# aiotdaan.net
KiCad netlist of a schematic drawn in EAGLE
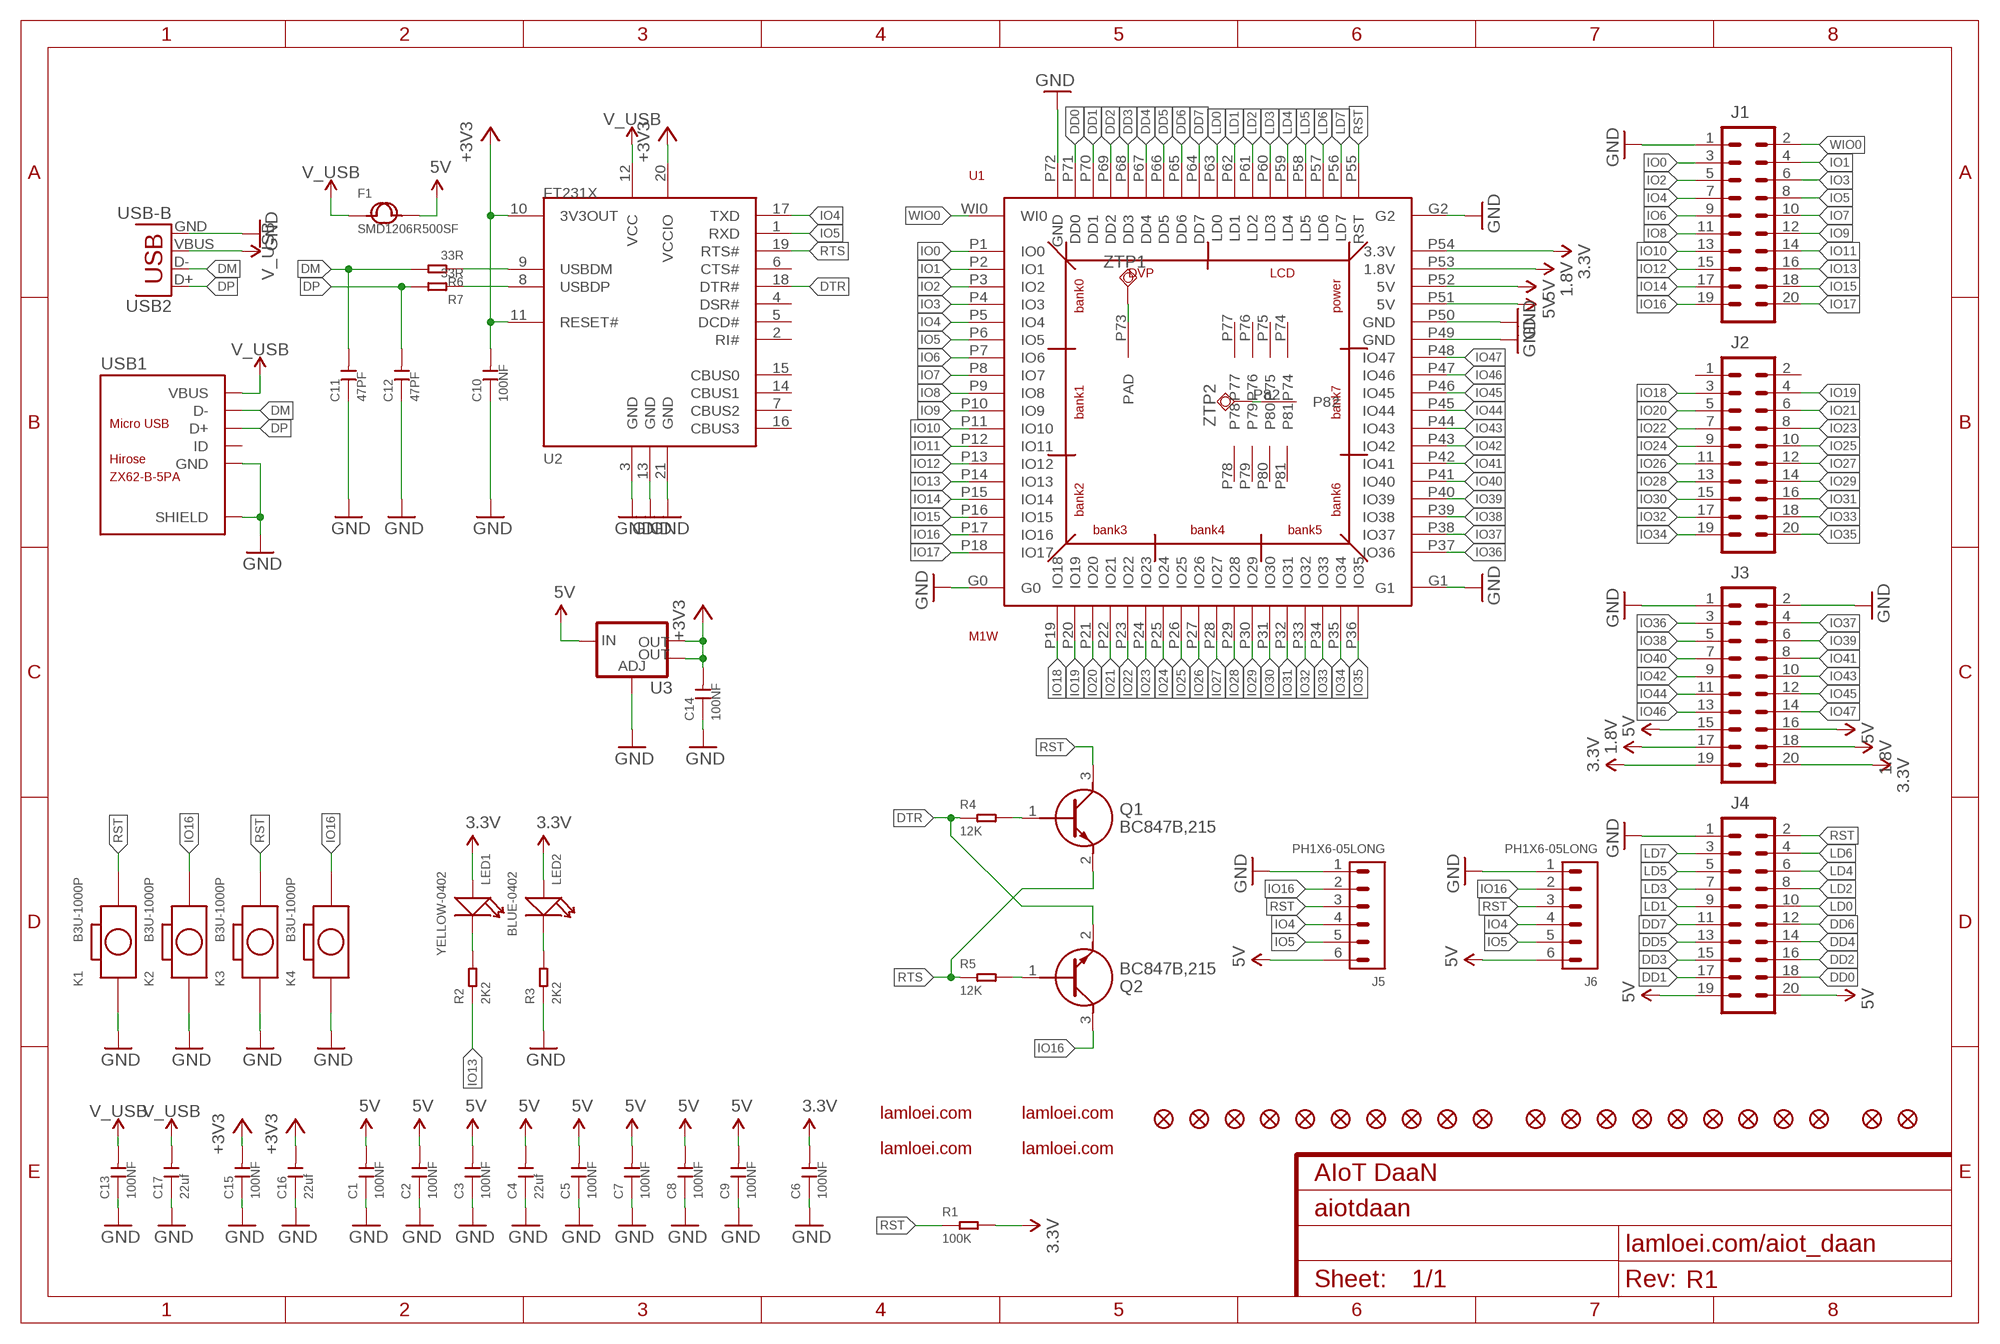
[diagram p0: schematic, sheet 1]

(export (version "E")
  (design (tool "Eeschema 10.0.6"))
  (components
    (comp (ref "C1")
      (value "100NF")
      (footprint "eagle-import:C0402")
      (fields (field (name "MPN") "CC0402JRNPO9BN470"))
      (libsource (lib "eagle-import") (part "CERAMIC-47PF-50V-5%-NP0(0402)"))
    )
    (comp (ref "C2")
      (value "100NF")
      (footprint "eagle-import:C0402")
      (fields (field (name "MPN") "CC0402JRNPO9BN470"))
      (libsource (lib "eagle-import") (part "CERAMIC-47PF-50V-5%-NP0(0402)"))
    )
    (comp (ref "C3")
      (value "100NF")
      (footprint "eagle-import:C0402")
      (fields (field (name "MPN") "CC0402JRNPO9BN470"))
      (libsource (lib "eagle-import") (part "CERAMIC-47PF-50V-5%-NP0(0402)"))
    )
    (comp (ref "C4")
      (value "22uf")
      (footprint "eagle-import:C0805")
      (fields (field (name "MPN") "CC0805MKX5R5BB226"))
      (libsource (lib "eagle-import") (part "CERAMIC-22UF-6.3V-20%-X5R(0805)"))
    )
    (comp (ref "C5")
      (value "100NF")
      (footprint "eagle-import:C0402")
      (fields (field (name "MPN") "CC0402JRNPO9BN470"))
      (libsource (lib "eagle-import") (part "CERAMIC-47PF-50V-5%-NP0(0402)"))
    )
    (comp (ref "C6")
      (value "100NF")
      (footprint "eagle-import:C0402")
      (fields (field (name "MPN") "CC0402JRNPO9BN470"))
      (libsource (lib "eagle-import") (part "CERAMIC-47PF-50V-5%-NP0(0402)"))
    )
    (comp (ref "C7")
      (value "100NF")
      (footprint "eagle-import:C0402")
      (fields (field (name "MPN") "CC0402JRNPO9BN470"))
      (libsource (lib "eagle-import") (part "CERAMIC-47PF-50V-5%-NP0(0402)"))
    )
    (comp (ref "C8")
      (value "100NF")
      (footprint "eagle-import:C0402")
      (fields (field (name "MPN") "CC0402JRNPO9BN470"))
      (libsource (lib "eagle-import") (part "CERAMIC-47PF-50V-5%-NP0(0402)"))
    )
    (comp (ref "C9")
      (value "100NF")
      (footprint "eagle-import:C0402")
      (fields (field (name "MPN") "CC0402JRNPO9BN470"))
      (libsource (lib "eagle-import") (part "CERAMIC-47PF-50V-5%-NP0(0402)"))
    )
    (comp (ref "C10")
      (value "100NF")
      (footprint "eagle-import:C0402")
      (fields (field (name "MPN") "CC0402JRNPO9BN470"))
      (libsource (lib "eagle-import") (part "CERAMIC-47PF-50V-5%-NP0(0402)"))
    )
    (comp (ref "C11")
      (value "47PF")
      (footprint "eagle-import:C0402")
      (fields (field (name "MPN") "CC0402JRNPO9BN470"))
      (libsource (lib "eagle-import") (part "CERAMIC-47PF-50V-5%-NP0(0402)"))
    )
    (comp (ref "C12")
      (value "47PF")
      (footprint "eagle-import:C0402")
      (fields (field (name "MPN") "CC0402JRNPO9BN470"))
      (libsource (lib "eagle-import") (part "CERAMIC-47PF-50V-5%-NP0(0402)"))
    )
    (comp (ref "C13")
      (value "100NF")
      (footprint "eagle-import:C0402")
      (fields (field (name "MPN") "CC0402JRNPO9BN470"))
      (libsource (lib "eagle-import") (part "CERAMIC-47PF-50V-5%-NP0(0402)"))
    )
    (comp (ref "C14")
      (value "100NF")
      (footprint "eagle-import:C0402")
      (fields (field (name "MPN") "CC0402JRNPO9BN470"))
      (libsource (lib "eagle-import") (part "CERAMIC-47PF-50V-5%-NP0(0402)"))
    )
    (comp (ref "C15")
      (value "100NF")
      (footprint "eagle-import:C0402")
      (fields (field (name "MPN") "CC0402JRNPO9BN470"))
      (libsource (lib "eagle-import") (part "CERAMIC-47PF-50V-5%-NP0(0402)"))
    )
    (comp (ref "C16")
      (value "22uf")
      (footprint "eagle-import:C0805")
      (fields (field (name "MPN") "CC0805MKX5R5BB226"))
      (libsource (lib "eagle-import") (part "CERAMIC-22UF-6.3V-20%-X5R(0805)"))
    )
    (comp (ref "C17")
      (value "22uf")
      (footprint "eagle-import:C0805")
      (fields (field (name "MPN") "CC0805MKX5R5BB226"))
      (libsource (lib "eagle-import") (part "CERAMIC-22UF-6.3V-20%-X5R(0805)"))
    )
    (comp (ref "F1")
      (value "SMD1206R500SF")
      (footprint "eagle-import:F1206")
      (libsource (lib "eagle-import") (part "SMD-PPTC-500MA(1206)"))
    )
    (comp (ref "J1")
      (value "M10X2")
      (footprint "eagle-import:2X10")
      (libsource (lib "eagle-import") (part "M10X2"))
    )
    (comp (ref "J2")
      (value "M10X2")
      (footprint "eagle-import:2X10")
      (libsource (lib "eagle-import") (part "M10X2"))
    )
    (comp (ref "J3")
      (value "M10X2")
      (footprint "eagle-import:2X10")
      (libsource (lib "eagle-import") (part "M10X2"))
    )
    (comp (ref "J4")
      (value "M10X2")
      (footprint "eagle-import:2X10")
      (libsource (lib "eagle-import") (part "M10X2"))
    )
    (comp (ref "J5")
      (value "PH1X6-05LONG")
      (footprint "eagle-import:PHL005-1-6")
      (libsource (lib "eagle-import") (part "PH1X6-05LONG"))
    )
    (comp (ref "J6")
      (value "PH1X6-05LONG")
      (footprint "eagle-import:PHL005-1-6")
      (libsource (lib "eagle-import") (part "PH1X6-05LONG"))
    )
    (comp (ref "K1")
      (value "B3U-1000P")
      (footprint "eagle-import:SW2-SMD-3.0X2.5X1.2+0.4MM")
      (libsource (lib "eagle-import") (part "SMD-BUTTON-WITHOUT-BOSS-(2P-3X2.5MM)"))
    )
    (comp (ref "K2")
      (value "B3U-1000P")
      (footprint "eagle-import:SW2-SMD-3.0X2.5X1.2+0.4MM")
      (libsource (lib "eagle-import") (part "SMD-BUTTON-WITHOUT-BOSS-(2P-3X2.5MM)"))
    )
    (comp (ref "K3")
      (value "B3U-1000P")
      (footprint "eagle-import:SW2-SMD-3.0X2.5X1.2+0.4MM")
      (libsource (lib "eagle-import") (part "SMD-BUTTON-WITHOUT-BOSS-(2P-3X2.5MM)"))
    )
    (comp (ref "K4")
      (value "B3U-1000P")
      (footprint "eagle-import:SW2-SMD-3.0X2.5X1.2+0.4MM")
      (libsource (lib "eagle-import") (part "SMD-BUTTON-WITHOUT-BOSS-(2P-3X2.5MM)"))
    )
    (comp (ref "LED1")
      (value "YELLOW-0402")
      (footprint "eagle-import:LED-0402")
      (fields (field (name "MPN") "BL-HB337A-AV-TRB"))
      (libsource (lib "eagle-import") (part "SMD-LED-CLEAR-BLUE(0402)"))
    )
    (comp (ref "LED2")
      (value "BLUE-0402")
      (footprint "eagle-import:LED-0402")
      (fields (field (name "MPN") "BL-HB337A-AV-TRB"))
      (libsource (lib "eagle-import") (part "SMD-LED-CLEAR-BLUE(0402)"))
    )
    (comp (ref "Q1")
      (value "BC847B,215")
      (footprint "eagle-import:SOT95P230X110-3N")
      (fields (field (name "RS_PART_NUMBER") "4367947P"))
      (libsource (lib "eagle-import") (part "BC847B,215"))
    )
    (comp (ref "Q2")
      (value "BC847B,215")
      (footprint "eagle-import:SOT95P230X110-3N")
      (fields (field (name "RS_PART_NUMBER") "4367947P"))
      (libsource (lib "eagle-import") (part "BC847B,215"))
    )
    (comp (ref "R1")
      (value "100K")
      (footprint "eagle-import:R0402")
      (fields (field (name "MPN") "RC0402FR-0722RL"))
      (libsource (lib "eagle-import") (part "SMD-RES-22R-1%-1/16W(0402)"))
    )
    (comp (ref "R2")
      (value "2K2")
      (footprint "eagle-import:R0402")
      (fields (field (name "MPN") "RC0402FR-0722RL"))
      (libsource (lib "eagle-import") (part "SMD-RES-22R-1%-1/16W(0402)"))
    )
    (comp (ref "R3")
      (value "2K2")
      (footprint "eagle-import:R0402")
      (fields (field (name "MPN") "RC0402FR-0722RL"))
      (libsource (lib "eagle-import") (part "SMD-RES-22R-1%-1/16W(0402)"))
    )
    (comp (ref "R4")
      (value "12K")
      (footprint "eagle-import:R0402")
      (fields (field (name "MPN") "RC0402FR-0722RL"))
      (libsource (lib "eagle-import") (part "SMD-RES-22R-1%-1/16W(0402)"))
    )
    (comp (ref "R5")
      (value "12K")
      (footprint "eagle-import:R0402")
      (fields (field (name "MPN") "RC0402FR-0722RL"))
      (libsource (lib "eagle-import") (part "SMD-RES-22R-1%-1/16W(0402)"))
    )
    (comp (ref "R6")
      (value "33R")
      (footprint "eagle-import:R0402")
      (fields (field (name "MPN") "RC0402FR-0722RL"))
      (libsource (lib "eagle-import") (part "SMD-RES-22R-1%-1/16W(0402)"))
    )
    (comp (ref "R7")
      (value "33R")
      (footprint "eagle-import:R0402")
      (fields (field (name "MPN") "RC0402FR-0722RL"))
      (libsource (lib "eagle-import") (part "SMD-RES-22R-1%-1/16W(0402)"))
    )
    (comp (ref "U1")
      (value "M1W")
      (footprint "eagle-import:M1W")
      (libsource (lib "eagle-import") (part "M1W"))
    )
    (comp (ref "U2")
      (value "FT231X-Q")
      (footprint "eagle-import:QFN20")
      (libsource (lib "eagle-import") (part "FT231X-Q"))
    )
    (comp (ref "U3")
      (value "V_REG_LM1117SOT223")
      (footprint "eagle-import:SOT223")
      (libsource (lib "eagle-import") (part "V_REG_LM1117SOT223"))
    )
    (comp (ref "USB1")
      (value "ZX62-B-5PA")
      (footprint "eagle-import:MICRO-USB5+6P-SMD-0.65-AB")
      (libsource (lib "eagle-import") (part "MICRO-USB-SMD(ZX62-B-5PA)"))
    )
    (comp (ref "USB2")
      (value "USB-B")
      (footprint "eagle-import:USB-B-PTH")
      (libsource (lib "eagle-import") (part "USBPTH"))
    )
    (comp (ref "ZFD1")
      (value "FIDUCIAL1X2")
      (footprint "eagle-import:FIDUCIAL-1X2")
      (libsource (lib "eagle-import") (part "FIDUCIAL1X2"))
    )
    (comp (ref "ZFD2")
      (value "FIDUCIAL1X2")
      (footprint "eagle-import:FIDUCIAL-1X2")
      (libsource (lib "eagle-import") (part "FIDUCIAL1X2"))
    )
    (comp (ref "ZFD3")
      (value "FIDUCIAL1X2")
      (footprint "eagle-import:FIDUCIAL-1X2")
      (libsource (lib "eagle-import") (part "FIDUCIAL1X2"))
    )
    (comp (ref "ZFD4")
      (value "FIDUCIAL1X2")
      (footprint "eagle-import:FIDUCIAL-1X2")
      (libsource (lib "eagle-import") (part "FIDUCIAL1X2"))
    )
    (comp (ref "ZFD5")
      (value "FIDUCIAL1X2")
      (footprint "eagle-import:FIDUCIAL-1X2")
      (libsource (lib "eagle-import") (part "FIDUCIAL1X2"))
    )
    (comp (ref "ZFD6")
      (value "FIDUCIAL1X2")
      (footprint "eagle-import:FIDUCIAL-1X2")
      (libsource (lib "eagle-import") (part "FIDUCIAL1X2"))
    )
    (comp (ref "ZFD7")
      (value "FIDUCIAL1X2")
      (footprint "eagle-import:FIDUCIAL-1X2")
      (libsource (lib "eagle-import") (part "FIDUCIAL1X2"))
    )
    (comp (ref "ZFD8")
      (value "FIDUCIAL1X2")
      (footprint "eagle-import:FIDUCIAL-1X2")
      (libsource (lib "eagle-import") (part "FIDUCIAL1X2"))
    )
    (comp (ref "ZFD9")
      (value "FIDUCIAL1X2")
      (footprint "eagle-import:FIDUCIAL-1X2")
      (libsource (lib "eagle-import") (part "FIDUCIAL1X2"))
    )
    (comp (ref "ZFD10")
      (value "FIDUCIAL1X2")
      (footprint "eagle-import:FIDUCIAL-1X2")
      (libsource (lib "eagle-import") (part "FIDUCIAL1X2"))
    )
    (comp (ref "ZFD11")
      (value "FIDUCIAL1X2")
      (footprint "eagle-import:FIDUCIAL-1X2")
      (libsource (lib "eagle-import") (part "FIDUCIAL1X2"))
    )
    (comp (ref "ZFD12")
      (value "FIDUCIAL1X2")
      (footprint "eagle-import:FIDUCIAL-1X2")
      (libsource (lib "eagle-import") (part "FIDUCIAL1X2"))
    )
    (comp (ref "ZFD13")
      (value "FIDUCIAL1X2")
      (footprint "eagle-import:FIDUCIAL-1X2")
      (libsource (lib "eagle-import") (part "FIDUCIAL1X2"))
    )
    (comp (ref "ZFD14")
      (value "FIDUCIAL1X2")
      (footprint "eagle-import:FIDUCIAL-1X2")
      (libsource (lib "eagle-import") (part "FIDUCIAL1X2"))
    )
    (comp (ref "ZFD15")
      (value "FIDUCIAL1X2")
      (footprint "eagle-import:FIDUCIAL-1X2")
      (libsource (lib "eagle-import") (part "FIDUCIAL1X2"))
    )
    (comp (ref "ZFD16")
      (value "FIDUCIAL1X2")
      (footprint "eagle-import:FIDUCIAL-1X2")
      (libsource (lib "eagle-import") (part "FIDUCIAL1X2"))
    )
    (comp (ref "ZFD17")
      (value "FIDUCIAL1X2")
      (footprint "eagle-import:FIDUCIAL-1X2")
      (libsource (lib "eagle-import") (part "FIDUCIAL1X2"))
    )
    (comp (ref "ZFD18")
      (value "FIDUCIAL1X2")
      (footprint "eagle-import:FIDUCIAL-1X2")
      (libsource (lib "eagle-import") (part "FIDUCIAL1X2"))
    )
    (comp (ref "ZFD19")
      (value "FIDUCIAL1X2")
      (footprint "eagle-import:FIDUCIAL-1X2")
      (libsource (lib "eagle-import") (part "FIDUCIAL1X2"))
    )
    (comp (ref "ZFD20")
      (value "FIDUCIAL1X2")
      (footprint "eagle-import:FIDUCIAL-1X2")
      (libsource (lib "eagle-import") (part "FIDUCIAL1X2"))
    )
    (comp (ref "ZFD21")
      (value "FIDUCIAL1X2")
      (footprint "eagle-import:FIDUCIAL-1X2")
      (libsource (lib "eagle-import") (part "FIDUCIAL1X2"))
    )
    (comp (ref "ZL1")
      (value "LAMLOEI_BIGLOGO")
      (footprint "eagle-import:LAMLOEI_BIGLOGO")
      (libsource (lib "eagle-import") (part "LAMLOEI_BIGLOGO"))
    )
    (comp (ref "ZL2")
      (value "LAMLOEI_BIGLOGO")
      (footprint "eagle-import:LAMLOEI_BIGLOGO")
      (libsource (lib "eagle-import") (part "LAMLOEI_BIGLOGO"))
    )
    (comp (ref "ZL3")
      (value "LAMLEOI_LOGO_3")
      (footprint "eagle-import:LAMLEOI_LOGO_3")
      (libsource (lib "eagle-import") (part "LAMLEOI_LOGO_3"))
    )
    (comp (ref "ZL4")
      (value "LAMLEOI_LOGO_3")
      (footprint "eagle-import:LAMLEOI_LOGO_3")
      (libsource (lib "eagle-import") (part "LAMLEOI_LOGO_3"))
    )
    (comp (ref "ZTP1")
      (value "TPSQTP20SQ")
      (footprint "eagle-import:TP20SQ")
      (libsource (lib "eagle-import") (part "TPSQTP20SQ"))
    )
    (comp (ref "ZTP2")
      (value "TPSQTP20SQ")
      (footprint "eagle-import:TP20SQ")
      (libsource (lib "eagle-import") (part "TPSQTP20SQ"))
    )
  )
  (nets
    (net (code "1") (name "+3V3") (class "Default")
      (node (ref "C10") (pin "2") (pinfunction "2_2") (pintype "passive"))
      (node (ref "C14") (pin "2") (pinfunction "2_2") (pintype "passive"))
      (node (ref "C15") (pin "2") (pinfunction "2_2") (pintype "passive"))
      (node (ref "C16") (pin "2") (pinfunction "2_2") (pintype "passive"))
      (node (ref "U2") (pin "10") (pinfunction "3V3OUT_10") (pintype "bidirectional"))
      (node (ref "U2") (pin "11") (pinfunction "RESET#_11") (pintype "bidirectional"))
      (node (ref "U2") (pin "20") (pinfunction "VCCIO_20") (pintype "bidirectional"))
      (node (ref "U3") (pin "2") (pinfunction "OUT_2") (pintype "output"))
      (node (ref "U3") (pin "4") (pinfunction "OUT_4") (pintype "output"))
    )
    (net (code "2") (name "1.8V") (class "Default")
      (node (ref "J3") (pin "17") (pinfunction "17_17") (pintype "passive"))
      (node (ref "J3") (pin "18") (pinfunction "18_18") (pintype "passive"))
      (node (ref "U1") (pin "P53") (pinfunction "1.8V_P53") (pintype "power_in"))
    )
    (net (code "3") (name "3.3V") (class "Default")
      (node (ref "C6") (pin "2") (pinfunction "2_2") (pintype "passive"))
      (node (ref "J3") (pin "19") (pinfunction "19_19") (pintype "passive"))
      (node (ref "J3") (pin "20") (pinfunction "20_20") (pintype "passive"))
      (node (ref "LED1") (pin "+") (pinfunction "+_+") (pintype "passive"))
      (node (ref "LED2") (pin "+") (pinfunction "+_+") (pintype "passive"))
      (node (ref "R1") (pin "2") (pinfunction "2_2") (pintype "passive"))
      (node (ref "U1") (pin "P54") (pinfunction "3.3V_P54") (pintype "power_in"))
    )
    (net (code "4") (name "5V") (class "Default")
      (node (ref "C1") (pin "2") (pinfunction "2_2") (pintype "passive"))
      (node (ref "C2") (pin "2") (pinfunction "2_2") (pintype "passive"))
      (node (ref "C3") (pin "2") (pinfunction "2_2") (pintype "passive"))
      (node (ref "C4") (pin "2") (pinfunction "2_2") (pintype "passive"))
      (node (ref "C5") (pin "2") (pinfunction "2_2") (pintype "passive"))
      (node (ref "C7") (pin "2") (pinfunction "2_2") (pintype "passive"))
      (node (ref "C8") (pin "2") (pinfunction "2_2") (pintype "passive"))
      (node (ref "C9") (pin "2") (pinfunction "2_2") (pintype "passive"))
      (node (ref "F1") (pin "2") (pinfunction "2_2") (pintype "bidirectional"))
      (node (ref "J3") (pin "15") (pinfunction "15_15") (pintype "passive"))
      (node (ref "J3") (pin "16") (pinfunction "16_16") (pintype "passive"))
      (node (ref "J4") (pin "19") (pinfunction "19_19") (pintype "passive"))
      (node (ref "J4") (pin "20") (pinfunction "20_20") (pintype "passive"))
      (node (ref "J5") (pin "6") (pinfunction "6_6") (pintype "bidirectional"))
      (node (ref "J6") (pin "6") (pinfunction "6_6") (pintype "bidirectional"))
      (node (ref "U1") (pin "P51") (pinfunction "5V_P51") (pintype "power_in"))
      (node (ref "U1") (pin "P52") (pinfunction "5V_P52") (pintype "power_in"))
      (node (ref "U3") (pin "3") (pinfunction "IN_3") (pintype "input"))
    )
    (net (code "5") (name "DD0") (class "Default")
      (node (ref "J4") (pin "18") (pinfunction "18_18") (pintype "passive"))
      (node (ref "U1") (pin "P71") (pinfunction "DD0_P71") (pintype "bidirectional"))
    )
    (net (code "6") (name "DD1") (class "Default")
      (node (ref "J4") (pin "17") (pinfunction "17_17") (pintype "passive"))
      (node (ref "U1") (pin "P70") (pinfunction "DD1_P70") (pintype "bidirectional"))
    )
    (net (code "7") (name "DD2") (class "Default")
      (node (ref "J4") (pin "16") (pinfunction "16_16") (pintype "passive"))
      (node (ref "U1") (pin "P69") (pinfunction "DD2_P69") (pintype "bidirectional"))
    )
    (net (code "8") (name "DD3") (class "Default")
      (node (ref "J4") (pin "15") (pinfunction "15_15") (pintype "passive"))
      (node (ref "U1") (pin "P68") (pinfunction "DD3_P68") (pintype "bidirectional"))
    )
    (net (code "9") (name "DD4") (class "Default")
      (node (ref "J4") (pin "14") (pinfunction "14_14") (pintype "passive"))
      (node (ref "U1") (pin "P67") (pinfunction "DD4_P67") (pintype "bidirectional"))
    )
    (net (code "10") (name "DD5") (class "Default")
      (node (ref "J4") (pin "13") (pinfunction "13_13") (pintype "passive"))
      (node (ref "U1") (pin "P66") (pinfunction "DD5_P66") (pintype "bidirectional"))
    )
    (net (code "11") (name "DD6") (class "Default")
      (node (ref "J4") (pin "12") (pinfunction "12_12") (pintype "passive"))
      (node (ref "U1") (pin "P65") (pinfunction "DD6_P65") (pintype "bidirectional"))
    )
    (net (code "12") (name "DD7") (class "Default")
      (node (ref "J4") (pin "11") (pinfunction "11_11") (pintype "passive"))
      (node (ref "U1") (pin "P64") (pinfunction "DD7_P64") (pintype "bidirectional"))
    )
    (net (code "13") (name "DM") (class "Default")
      (node (ref "C11") (pin "2") (pinfunction "2_2") (pintype "passive"))
      (node (ref "R6") (pin "2") (pinfunction "2_2") (pintype "passive"))
      (node (ref "USB1") (pin "2") (pinfunction "D-_2") (pintype "bidirectional"))
      (node (ref "USB2") (pin "D-") (pinfunction "D-_D-") (pintype "bidirectional"))
    )
    (net (code "14") (name "DP") (class "Default")
      (node (ref "C12") (pin "2") (pinfunction "2_2") (pintype "passive"))
      (node (ref "R7") (pin "2") (pinfunction "2_2") (pintype "passive"))
      (node (ref "USB1") (pin "3") (pinfunction "D+_3") (pintype "bidirectional"))
      (node (ref "USB2") (pin "D+") (pinfunction "D+_D+") (pintype "bidirectional"))
    )
    (net (code "15") (name "DTR") (class "Default")
      (node (ref "Q2") (pin "2") (pinfunction "E_2") (pintype "bidirectional"))
      (node (ref "R4") (pin "1") (pinfunction "1_1") (pintype "passive"))
      (node (ref "U2") (pin "18") (pinfunction "DTR#_18") (pintype "bidirectional"))
    )
    (net (code "16") (name "GND") (class "Default")
      (node (ref "C1") (pin "1") (pinfunction "1_1") (pintype "passive"))
      (node (ref "C10") (pin "1") (pinfunction "1_1") (pintype "passive"))
      (node (ref "C11") (pin "1") (pinfunction "1_1") (pintype "passive"))
      (node (ref "C12") (pin "1") (pinfunction "1_1") (pintype "passive"))
      (node (ref "C13") (pin "1") (pinfunction "1_1") (pintype "passive"))
      (node (ref "C14") (pin "1") (pinfunction "1_1") (pintype "passive"))
      (node (ref "C15") (pin "1") (pinfunction "1_1") (pintype "passive"))
      (node (ref "C16") (pin "1") (pinfunction "1_1") (pintype "passive"))
      (node (ref "C17") (pin "1") (pinfunction "1_1") (pintype "passive"))
      (node (ref "C2") (pin "1") (pinfunction "1_1") (pintype "passive"))
      (node (ref "C3") (pin "1") (pinfunction "1_1") (pintype "passive"))
      (node (ref "C4") (pin "1") (pinfunction "1_1") (pintype "passive"))
      (node (ref "C5") (pin "1") (pinfunction "1_1") (pintype "passive"))
      (node (ref "C6") (pin "1") (pinfunction "1_1") (pintype "passive"))
      (node (ref "C7") (pin "1") (pinfunction "1_1") (pintype "passive"))
      (node (ref "C8") (pin "1") (pinfunction "1_1") (pintype "passive"))
      (node (ref "C9") (pin "1") (pinfunction "1_1") (pintype "passive"))
      (node (ref "J1") (pin "1") (pinfunction "1_1") (pintype "passive"))
      (node (ref "J3") (pin "1") (pinfunction "1_1") (pintype "passive"))
      (node (ref "J3") (pin "2") (pinfunction "2_2") (pintype "passive"))
      (node (ref "J4") (pin "1") (pinfunction "1_1") (pintype "passive"))
      (node (ref "J5") (pin "1") (pinfunction "1_1") (pintype "bidirectional"))
      (node (ref "J6") (pin "1") (pinfunction "1_1") (pintype "bidirectional"))
      (node (ref "K1") (pin "1") (pinfunction "1_1") (pintype "bidirectional"))
      (node (ref "K2") (pin "1") (pinfunction "1_1") (pintype "bidirectional"))
      (node (ref "K3") (pin "1") (pinfunction "1_1") (pintype "bidirectional"))
      (node (ref "K4") (pin "1") (pinfunction "1_1") (pintype "bidirectional"))
      (node (ref "R3") (pin "1") (pinfunction "1_1") (pintype "passive"))
      (node (ref "U1") (pin "G0") (pinfunction "G0_G0") (pintype "power_in"))
      (node (ref "U1") (pin "G1") (pinfunction "G1_G1") (pintype "power_in"))
      (node (ref "U1") (pin "G2") (pinfunction "G2_G2") (pintype "power_in"))
      (node (ref "U1") (pin "P49") (pinfunction "GND_P49") (pintype "power_in"))
      (node (ref "U1") (pin "P50") (pinfunction "GND_P50") (pintype "power_in"))
      (node (ref "U1") (pin "P72") (pinfunction "GND_P72") (pintype "power_in"))
      (node (ref "U2") (pin "13") (pinfunction "GND_13") (pintype "bidirectional"))
      (node (ref "U2") (pin "21") (pinfunction "GND_21") (pintype "bidirectional"))
      (node (ref "U2") (pin "3") (pinfunction "GND_3") (pintype "bidirectional"))
      (node (ref "U3") (pin "1") (pinfunction "ADJ_1") (pintype "input"))
      (node (ref "USB1") (pin "5") (pinfunction "GND_5") (pintype "power_in"))
      (node (ref "USB1") (pin "P1") (pinfunction "SHIELD_P1") (pintype "power_in"))
      (node (ref "USB1") (pin "P2") (pinfunction "SHIELD_P2") (pintype "power_in"))
      (node (ref "USB1") (pin "P3") (pinfunction "SHIELD_P3") (pintype "power_in"))
      (node (ref "USB1") (pin "P4") (pinfunction "SHIELD_P4") (pintype "power_in"))
      (node (ref "USB1") (pin "P5") (pinfunction "SHIELD_P5") (pintype "power_in"))
      (node (ref "USB1") (pin "P6") (pinfunction "SHIELD_P6") (pintype "power_in"))
      (node (ref "USB2") (pin "GND") (pinfunction "GND_GND") (pintype "bidirectional"))
    )
    (net (code "17") (name "IO0") (class "Default")
      (node (ref "J1") (pin "3") (pinfunction "3_3") (pintype "passive"))
      (node (ref "U1") (pin "P1") (pinfunction "IO0_P1") (pintype "bidirectional"))
    )
    (net (code "18") (name "IO1") (class "Default")
      (node (ref "J1") (pin "4") (pinfunction "4_4") (pintype "passive"))
      (node (ref "U1") (pin "P2") (pinfunction "IO1_P2") (pintype "bidirectional"))
    )
    (net (code "19") (name "IO2") (class "Default")
      (node (ref "J1") (pin "5") (pinfunction "5_5") (pintype "passive"))
      (node (ref "U1") (pin "P3") (pinfunction "IO2_P3") (pintype "bidirectional"))
    )
    (net (code "20") (name "IO3") (class "Default")
      (node (ref "J1") (pin "6") (pinfunction "6_6") (pintype "passive"))
      (node (ref "U1") (pin "P4") (pinfunction "IO3_P4") (pintype "bidirectional"))
    )
    (net (code "21") (name "IO4") (class "Default")
      (node (ref "J1") (pin "7") (pinfunction "7_7") (pintype "passive"))
      (node (ref "J5") (pin "4") (pinfunction "4_4") (pintype "bidirectional"))
      (node (ref "J6") (pin "4") (pinfunction "4_4") (pintype "bidirectional"))
      (node (ref "U1") (pin "P5") (pinfunction "IO4_P5") (pintype "bidirectional"))
      (node (ref "U2") (pin "17") (pinfunction "TXD_17") (pintype "bidirectional"))
    )
    (net (code "22") (name "IO5") (class "Default")
      (node (ref "J1") (pin "8") (pinfunction "8_8") (pintype "passive"))
      (node (ref "J5") (pin "5") (pinfunction "5_5") (pintype "bidirectional"))
      (node (ref "J6") (pin "5") (pinfunction "5_5") (pintype "bidirectional"))
      (node (ref "U1") (pin "P6") (pinfunction "IO5_P6") (pintype "bidirectional"))
      (node (ref "U2") (pin "1") (pinfunction "RXD_1") (pintype "bidirectional"))
    )
    (net (code "23") (name "IO6") (class "Default")
      (node (ref "J1") (pin "9") (pinfunction "9_9") (pintype "passive"))
      (node (ref "U1") (pin "P7") (pinfunction "IO6_P7") (pintype "bidirectional"))
    )
    (net (code "24") (name "IO7") (class "Default")
      (node (ref "J1") (pin "10") (pinfunction "10_10") (pintype "passive"))
      (node (ref "U1") (pin "P8") (pinfunction "IO7_P8") (pintype "bidirectional"))
    )
    (net (code "25") (name "IO8") (class "Default")
      (node (ref "J1") (pin "11") (pinfunction "11_11") (pintype "passive"))
      (node (ref "U1") (pin "P9") (pinfunction "IO8_P9") (pintype "bidirectional"))
    )
    (net (code "26") (name "IO9") (class "Default")
      (node (ref "J1") (pin "12") (pinfunction "12_12") (pintype "passive"))
      (node (ref "U1") (pin "P10") (pinfunction "IO9_P10") (pintype "bidirectional"))
    )
    (net (code "27") (name "IO10") (class "Default")
      (node (ref "J1") (pin "13") (pinfunction "13_13") (pintype "passive"))
      (node (ref "U1") (pin "P11") (pinfunction "IO10_P11") (pintype "bidirectional"))
    )
    (net (code "28") (name "IO11") (class "Default")
      (node (ref "J1") (pin "14") (pinfunction "14_14") (pintype "passive"))
      (node (ref "U1") (pin "P12") (pinfunction "IO11_P12") (pintype "bidirectional"))
    )
    (net (code "29") (name "IO12") (class "Default")
      (node (ref "J1") (pin "15") (pinfunction "15_15") (pintype "passive"))
      (node (ref "U1") (pin "P13") (pinfunction "IO12_P13") (pintype "bidirectional"))
    )
    (net (code "30") (name "IO13") (class "Default")
      (node (ref "J1") (pin "16") (pinfunction "16_16") (pintype "passive"))
      (node (ref "R2") (pin "1") (pinfunction "1_1") (pintype "passive"))
      (node (ref "U1") (pin "P14") (pinfunction "IO13_P14") (pintype "bidirectional"))
    )
    (net (code "31") (name "IO14") (class "Default")
      (node (ref "J1") (pin "17") (pinfunction "17_17") (pintype "passive"))
      (node (ref "U1") (pin "P15") (pinfunction "IO14_P15") (pintype "bidirectional"))
    )
    (net (code "32") (name "IO15") (class "Default")
      (node (ref "J1") (pin "18") (pinfunction "18_18") (pintype "passive"))
      (node (ref "U1") (pin "P16") (pinfunction "IO15_P16") (pintype "bidirectional"))
    )
    (net (code "33") (name "IO16") (class "Default")
      (node (ref "J1") (pin "19") (pinfunction "19_19") (pintype "passive"))
      (node (ref "J5") (pin "2") (pinfunction "2_2") (pintype "bidirectional"))
      (node (ref "J6") (pin "2") (pinfunction "2_2") (pintype "bidirectional"))
      (node (ref "K2") (pin "2") (pinfunction "2_2") (pintype "bidirectional"))
      (node (ref "K4") (pin "2") (pinfunction "2_2") (pintype "bidirectional"))
      (node (ref "Q2") (pin "3") (pinfunction "C_3") (pintype "bidirectional"))
      (node (ref "U1") (pin "P17") (pinfunction "IO16_P17") (pintype "bidirectional"))
    )
    (net (code "34") (name "IO17") (class "Default")
      (node (ref "J1") (pin "20") (pinfunction "20_20") (pintype "passive"))
      (node (ref "U1") (pin "P18") (pinfunction "IO17_P18") (pintype "bidirectional"))
    )
    (net (code "35") (name "IO18") (class "Default")
      (node (ref "J2") (pin "3") (pinfunction "3_3") (pintype "passive"))
      (node (ref "U1") (pin "P19") (pinfunction "IO18_P19") (pintype "bidirectional"))
    )
    (net (code "36") (name "IO19") (class "Default")
      (node (ref "J2") (pin "4") (pinfunction "4_4") (pintype "passive"))
      (node (ref "U1") (pin "P20") (pinfunction "IO19_P20") (pintype "bidirectional"))
    )
    (net (code "37") (name "IO20") (class "Default")
      (node (ref "J2") (pin "5") (pinfunction "5_5") (pintype "passive"))
      (node (ref "U1") (pin "P21") (pinfunction "IO20_P21") (pintype "bidirectional"))
    )
    (net (code "38") (name "IO21") (class "Default")
      (node (ref "J2") (pin "6") (pinfunction "6_6") (pintype "passive"))
      (node (ref "U1") (pin "P22") (pinfunction "IO21_P22") (pintype "bidirectional"))
    )
    (net (code "39") (name "IO22") (class "Default")
      (node (ref "J2") (pin "7") (pinfunction "7_7") (pintype "passive"))
      (node (ref "U1") (pin "P23") (pinfunction "IO22_P23") (pintype "bidirectional"))
    )
    (net (code "40") (name "IO23") (class "Default")
      (node (ref "J2") (pin "8") (pinfunction "8_8") (pintype "passive"))
      (node (ref "U1") (pin "P24") (pinfunction "IO23_P24") (pintype "bidirectional"))
    )
    (net (code "41") (name "IO24") (class "Default")
      (node (ref "J2") (pin "9") (pinfunction "9_9") (pintype "passive"))
      (node (ref "U1") (pin "P25") (pinfunction "IO24_P25") (pintype "bidirectional"))
    )
    (net (code "42") (name "IO25") (class "Default")
      (node (ref "J2") (pin "10") (pinfunction "10_10") (pintype "passive"))
      (node (ref "U1") (pin "P26") (pinfunction "IO25_P26") (pintype "bidirectional"))
    )
    (net (code "43") (name "IO26") (class "Default")
      (node (ref "J2") (pin "11") (pinfunction "11_11") (pintype "passive"))
      (node (ref "U1") (pin "P27") (pinfunction "IO26_P27") (pintype "bidirectional"))
    )
    (net (code "44") (name "IO27") (class "Default")
      (node (ref "J2") (pin "12") (pinfunction "12_12") (pintype "passive"))
      (node (ref "U1") (pin "P28") (pinfunction "IO27_P28") (pintype "bidirectional"))
    )
    (net (code "45") (name "IO28") (class "Default")
      (node (ref "J2") (pin "13") (pinfunction "13_13") (pintype "passive"))
      (node (ref "U1") (pin "P29") (pinfunction "IO28_P29") (pintype "bidirectional"))
    )
    (net (code "46") (name "IO29") (class "Default")
      (node (ref "J2") (pin "14") (pinfunction "14_14") (pintype "passive"))
      (node (ref "U1") (pin "P30") (pinfunction "IO29_P30") (pintype "bidirectional"))
    )
    (net (code "47") (name "IO30") (class "Default")
      (node (ref "J2") (pin "15") (pinfunction "15_15") (pintype "passive"))
      (node (ref "U1") (pin "P31") (pinfunction "IO30_P31") (pintype "bidirectional"))
    )
    (net (code "48") (name "IO31") (class "Default")
      (node (ref "J2") (pin "16") (pinfunction "16_16") (pintype "passive"))
      (node (ref "U1") (pin "P32") (pinfunction "IO31_P32") (pintype "bidirectional"))
    )
    (net (code "49") (name "IO32") (class "Default")
      (node (ref "J2") (pin "17") (pinfunction "17_17") (pintype "passive"))
      (node (ref "U1") (pin "P33") (pinfunction "IO32_P33") (pintype "bidirectional"))
    )
    (net (code "50") (name "IO33") (class "Default")
      (node (ref "J2") (pin "18") (pinfunction "18_18") (pintype "passive"))
      (node (ref "U1") (pin "P34") (pinfunction "IO33_P34") (pintype "bidirectional"))
    )
    (net (code "51") (name "IO34") (class "Default")
      (node (ref "J2") (pin "19") (pinfunction "19_19") (pintype "passive"))
      (node (ref "U1") (pin "P35") (pinfunction "IO34_P35") (pintype "bidirectional"))
    )
    (net (code "52") (name "IO35") (class "Default")
      (node (ref "J2") (pin "20") (pinfunction "20_20") (pintype "passive"))
      (node (ref "U1") (pin "P36") (pinfunction "IO35_P36") (pintype "bidirectional"))
    )
    (net (code "53") (name "IO36") (class "Default")
      (node (ref "J3") (pin "3") (pinfunction "3_3") (pintype "passive"))
      (node (ref "U1") (pin "P37") (pinfunction "IO36_P37") (pintype "bidirectional"))
    )
    (net (code "54") (name "IO37") (class "Default")
      (node (ref "J3") (pin "4") (pinfunction "4_4") (pintype "passive"))
      (node (ref "U1") (pin "P38") (pinfunction "IO37_P38") (pintype "bidirectional"))
    )
    (net (code "55") (name "IO38") (class "Default")
      (node (ref "J3") (pin "5") (pinfunction "5_5") (pintype "passive"))
      (node (ref "U1") (pin "P39") (pinfunction "IO38_P39") (pintype "bidirectional"))
    )
    (net (code "56") (name "IO39") (class "Default")
      (node (ref "J3") (pin "6") (pinfunction "6_6") (pintype "passive"))
      (node (ref "U1") (pin "P40") (pinfunction "IO39_P40") (pintype "bidirectional"))
    )
    (net (code "57") (name "IO40") (class "Default")
      (node (ref "J3") (pin "7") (pinfunction "7_7") (pintype "passive"))
      (node (ref "U1") (pin "P41") (pinfunction "IO40_P41") (pintype "bidirectional"))
    )
    (net (code "58") (name "IO41") (class "Default")
      (node (ref "J3") (pin "8") (pinfunction "8_8") (pintype "passive"))
      (node (ref "U1") (pin "P42") (pinfunction "IO41_P42") (pintype "bidirectional"))
    )
    (net (code "59") (name "IO42") (class "Default")
      (node (ref "J3") (pin "9") (pinfunction "9_9") (pintype "passive"))
      (node (ref "U1") (pin "P43") (pinfunction "IO42_P43") (pintype "bidirectional"))
    )
    (net (code "60") (name "IO43") (class "Default")
      (node (ref "J3") (pin "10") (pinfunction "10_10") (pintype "passive"))
      (node (ref "U1") (pin "P44") (pinfunction "IO43_P44") (pintype "bidirectional"))
    )
    (net (code "61") (name "IO44") (class "Default")
      (node (ref "J3") (pin "11") (pinfunction "11_11") (pintype "passive"))
      (node (ref "U1") (pin "P45") (pinfunction "IO44_P45") (pintype "bidirectional"))
    )
    (net (code "62") (name "IO45") (class "Default")
      (node (ref "J3") (pin "12") (pinfunction "12_12") (pintype "passive"))
      (node (ref "U1") (pin "P46") (pinfunction "IO45_P46") (pintype "bidirectional"))
    )
    (net (code "63") (name "IO46") (class "Default")
      (node (ref "J3") (pin "13") (pinfunction "13_13") (pintype "passive"))
      (node (ref "U1") (pin "P47") (pinfunction "IO46_P47") (pintype "bidirectional"))
    )
    (net (code "64") (name "IO47") (class "Default")
      (node (ref "J3") (pin "14") (pinfunction "14_14") (pintype "passive"))
      (node (ref "U1") (pin "P48") (pinfunction "IO47_P48") (pintype "bidirectional"))
    )
    (net (code "65") (name "LD0") (class "Default")
      (node (ref "J4") (pin "10") (pinfunction "10_10") (pintype "passive"))
      (node (ref "U1") (pin "P63") (pinfunction "LD0_P63") (pintype "bidirectional"))
    )
    (net (code "66") (name "LD1") (class "Default")
      (node (ref "J4") (pin "9") (pinfunction "9_9") (pintype "passive"))
      (node (ref "U1") (pin "P62") (pinfunction "LD1_P62") (pintype "bidirectional"))
    )
    (net (code "67") (name "LD2") (class "Default")
      (node (ref "J4") (pin "8") (pinfunction "8_8") (pintype "passive"))
      (node (ref "U1") (pin "P61") (pinfunction "LD2_P61") (pintype "bidirectional"))
    )
    (net (code "68") (name "LD3") (class "Default")
      (node (ref "J4") (pin "7") (pinfunction "7_7") (pintype "passive"))
      (node (ref "U1") (pin "P60") (pinfunction "LD3_P60") (pintype "bidirectional"))
    )
    (net (code "69") (name "LD4") (class "Default")
      (node (ref "J4") (pin "6") (pinfunction "6_6") (pintype "passive"))
      (node (ref "U1") (pin "P59") (pinfunction "LD4_P59") (pintype "bidirectional"))
    )
    (net (code "70") (name "LD5") (class "Default")
      (node (ref "J4") (pin "5") (pinfunction "5_5") (pintype "passive"))
      (node (ref "U1") (pin "P58") (pinfunction "LD5_P58") (pintype "bidirectional"))
    )
    (net (code "71") (name "LD6") (class "Default")
      (node (ref "J4") (pin "4") (pinfunction "4_4") (pintype "passive"))
      (node (ref "U1") (pin "P57") (pinfunction "LD6_P57") (pintype "bidirectional"))
    )
    (net (code "72") (name "LD7") (class "Default")
      (node (ref "J4") (pin "3") (pinfunction "3_3") (pintype "passive"))
      (node (ref "U1") (pin "P56") (pinfunction "LD7_P56") (pintype "bidirectional"))
    )
    (net (code "73") (name "Net-(LED1-Pad-)") (class "Default")
      (node (ref "LED1") (pin "-") (pinfunction "-_-") (pintype "passive"))
      (node (ref "R2") (pin "2") (pinfunction "2_2") (pintype "passive"))
    )
    (net (code "74") (name "Net-(LED2-Pad-)") (class "Default")
      (node (ref "LED2") (pin "-") (pinfunction "-_-") (pintype "passive"))
      (node (ref "R3") (pin "2") (pinfunction "2_2") (pintype "passive"))
    )
    (net (code "75") (name "Net-(Q1-B)") (class "Default")
      (node (ref "Q1") (pin "1") (pinfunction "B_1") (pintype "bidirectional"))
      (node (ref "R4") (pin "2") (pinfunction "2_2") (pintype "passive"))
    )
    (net (code "76") (name "Net-(Q2-B)") (class "Default")
      (node (ref "Q2") (pin "1") (pinfunction "B_1") (pintype "bidirectional"))
      (node (ref "R5") (pin "2") (pinfunction "2_2") (pintype "passive"))
    )
    (net (code "77") (name "Net-(U1-PAD)") (class "Default")
      (node (ref "U1") (pin "P73") (pinfunction "PAD_P73") (pintype "bidirectional"))
      (node (ref "ZTP1") (pin "TP") (pinfunction "TP_TP") (pintype "input"))
    )
    (net (code "78") (name "Net-(U1-PadP82)") (class "Default")
      (node (ref "U1") (pin "P82") (pinfunction "P82_P82") (pintype "bidirectional"))
      (node (ref "ZTP2") (pin "TP") (pinfunction "TP_TP") (pintype "input"))
    )
    (net (code "79") (name "Net-(U2-USBDM)") (class "Default")
      (node (ref "R6") (pin "1") (pinfunction "1_1") (pintype "passive"))
      (node (ref "U2") (pin "9") (pinfunction "USBDM_9") (pintype "bidirectional"))
    )
    (net (code "80") (name "Net-(U2-USBDP)") (class "Default")
      (node (ref "R7") (pin "1") (pinfunction "1_1") (pintype "passive"))
      (node (ref "U2") (pin "8") (pinfunction "USBDP_8") (pintype "bidirectional"))
    )
    (net (code "81") (name "RST") (class "Default")
      (node (ref "J4") (pin "2") (pinfunction "2_2") (pintype "passive"))
      (node (ref "J5") (pin "3") (pinfunction "3_3") (pintype "bidirectional"))
      (node (ref "J6") (pin "3") (pinfunction "3_3") (pintype "bidirectional"))
      (node (ref "K1") (pin "2") (pinfunction "2_2") (pintype "bidirectional"))
      (node (ref "K3") (pin "2") (pinfunction "2_2") (pintype "bidirectional"))
      (node (ref "Q1") (pin "3") (pinfunction "C_3") (pintype "bidirectional"))
      (node (ref "R1") (pin "1") (pinfunction "1_1") (pintype "passive"))
      (node (ref "U1") (pin "P55") (pinfunction "RST_P55") (pintype "bidirectional"))
    )
    (net (code "82") (name "RTS") (class "Default")
      (node (ref "Q1") (pin "2") (pinfunction "E_2") (pintype "bidirectional"))
      (node (ref "R5") (pin "1") (pinfunction "1_1") (pintype "passive"))
      (node (ref "U2") (pin "19") (pinfunction "RTS#_19") (pintype "bidirectional"))
    )
    (net (code "83") (name "V_USB") (class "Default")
      (node (ref "C13") (pin "2") (pinfunction "2_2") (pintype "passive"))
      (node (ref "C17") (pin "2") (pinfunction "2_2") (pintype "passive"))
      (node (ref "F1") (pin "1") (pinfunction "1_1") (pintype "bidirectional"))
      (node (ref "U2") (pin "12") (pinfunction "VCC_12") (pintype "bidirectional"))
      (node (ref "USB1") (pin "1") (pinfunction "VBUS_1") (pintype "power_in"))
      (node (ref "USB2") (pin "VBUS") (pinfunction "VBUS_VBUS") (pintype "bidirectional"))
    )
    (net (code "84") (name "WIO0") (class "Default")
      (node (ref "J1") (pin "2") (pinfunction "2_2") (pintype "passive"))
      (node (ref "U1") (pin "WI0") (pinfunction "WI0_WI0") (pintype "bidirectional"))
    )
    (net (code "85") (name "unconnected-(J2-Pad1)") (class "Default")
      (node (ref "J2") (pin "1") (pinfunction "1_1") (pintype "passive"))
    )
    (net (code "86") (name "unconnected-(J2-Pad2)") (class "Default")
      (node (ref "J2") (pin "2") (pinfunction "2_2") (pintype "passive"))
    )
    (net (code "87") (name "unconnected-(U1-PadP74)") (class "Default")
      (node (ref "U1") (pin "P74") (pinfunction "P74_P74") (pintype "bidirectional"))
    )
    (net (code "88") (name "unconnected-(U1-PadP75)") (class "Default")
      (node (ref "U1") (pin "P75") (pinfunction "P75_P75") (pintype "bidirectional"))
    )
    (net (code "89") (name "unconnected-(U1-PadP76)") (class "Default")
      (node (ref "U1") (pin "P76") (pinfunction "P76_P76") (pintype "bidirectional"))
    )
    (net (code "90") (name "unconnected-(U1-PadP77)") (class "Default")
      (node (ref "U1") (pin "P77") (pinfunction "P77_P77") (pintype "bidirectional"))
    )
    (net (code "91") (name "unconnected-(U1-PadP78)") (class "Default")
      (node (ref "U1") (pin "P78") (pinfunction "P78_P78") (pintype "bidirectional"))
    )
    (net (code "92") (name "unconnected-(U1-PadP79)") (class "Default")
      (node (ref "U1") (pin "P79") (pinfunction "P79_P79") (pintype "bidirectional"))
    )
    (net (code "93") (name "unconnected-(U1-PadP80)") (class "Default")
      (node (ref "U1") (pin "P80") (pinfunction "P80_P80") (pintype "bidirectional"))
    )
    (net (code "94") (name "unconnected-(U1-PadP81)") (class "Default")
      (node (ref "U1") (pin "P81") (pinfunction "P81_P81") (pintype "bidirectional"))
    )
    (net (code "95") (name "unconnected-(U2-CBUS0-Pad15)") (class "Default")
      (node (ref "U2") (pin "15") (pinfunction "CBUS0_15") (pintype "bidirectional"))
    )
    (net (code "96") (name "unconnected-(U2-CBUS1-Pad14)") (class "Default")
      (node (ref "U2") (pin "14") (pinfunction "CBUS1_14") (pintype "bidirectional"))
    )
    (net (code "97") (name "unconnected-(U2-CBUS2-Pad7)") (class "Default")
      (node (ref "U2") (pin "7") (pinfunction "CBUS2_7") (pintype "bidirectional"))
    )
    (net (code "98") (name "unconnected-(U2-CBUS3-Pad16)") (class "Default")
      (node (ref "U2") (pin "16") (pinfunction "CBUS3_16") (pintype "bidirectional"))
    )
    (net (code "99") (name "unconnected-(U2-CTS#-Pad6)") (class "Default")
      (node (ref "U2") (pin "6") (pinfunction "CTS#_6") (pintype "bidirectional"))
    )
    (net (code "100") (name "unconnected-(U2-DCD#-Pad5)") (class "Default")
      (node (ref "U2") (pin "5") (pinfunction "DCD#_5") (pintype "bidirectional"))
    )
    (net (code "101") (name "unconnected-(U2-DSR#-Pad4)") (class "Default")
      (node (ref "U2") (pin "4") (pinfunction "DSR#_4") (pintype "bidirectional"))
    )
    (net (code "102") (name "unconnected-(U2-RI#-Pad2)") (class "Default")
      (node (ref "U2") (pin "2") (pinfunction "RI#_2") (pintype "bidirectional"))
    )
    (net (code "103") (name "unconnected-(USB1-ID-Pad4)") (class "Default")
      (node (ref "USB1") (pin "4") (pinfunction "ID_4") (pintype "bidirectional"))
    )
  )
)
